# Qwiic_Multi_Port_Board.net
KiCad netlist of a schematic drawn in EAGLE
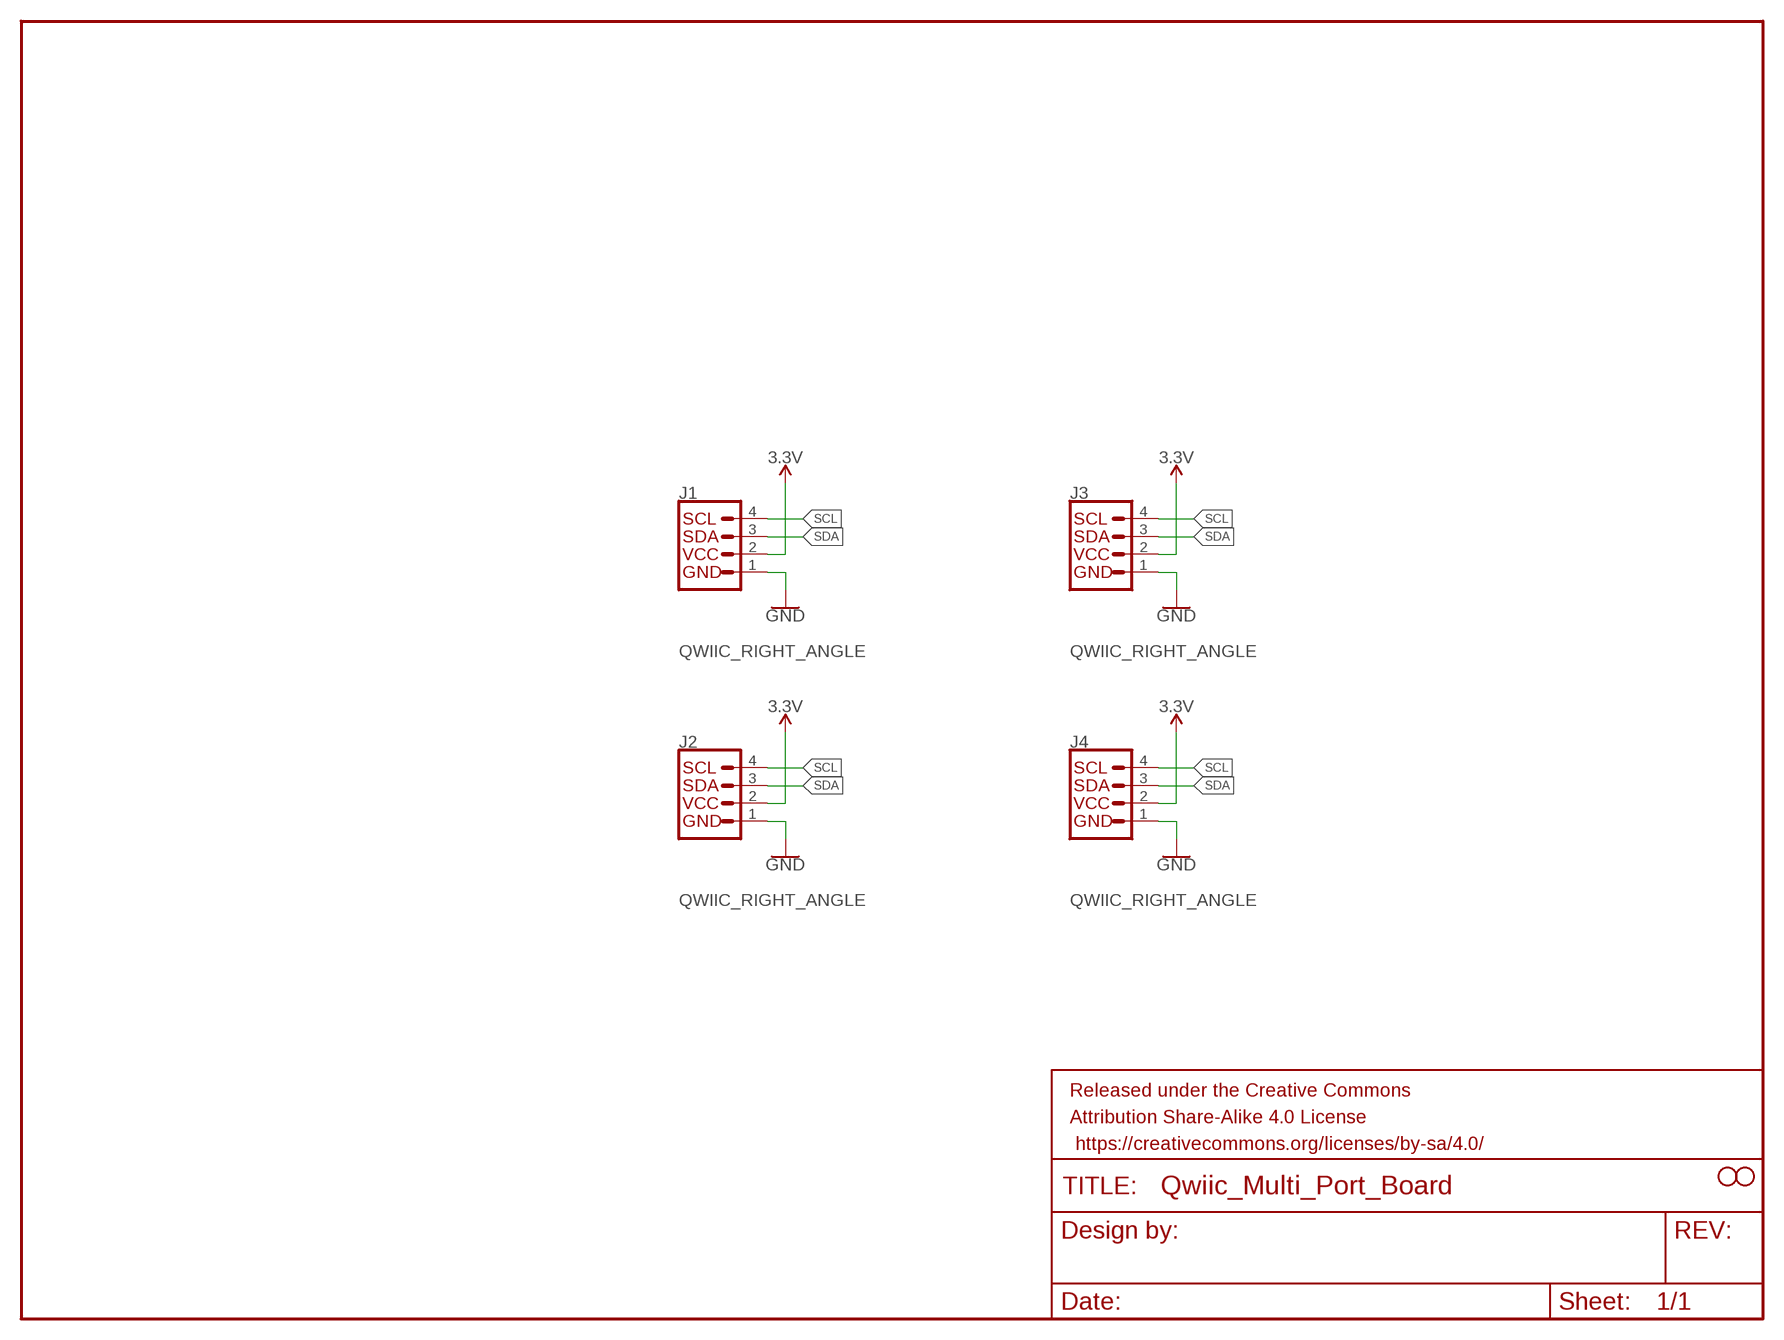
[diagram p0: schematic, sheet 1]

(export (version "E")
  (design (tool "Eeschema 10.0.6"))
  (components
    (comp (ref "FRAME1")
      (value "FRAME-LETTER")
      (footprint "eagle-import:CREATIVE_COMMONS")
      (libsource (lib "eagle-import") (part "FRAME-LETTER"))
    )
    (comp (ref "H1")
      (value "STAND-OFFTIGHT")
      (footprint "eagle-import:STAND-OFF-TIGHT")
      (libsource (lib "eagle-import") (part "STAND-OFFTIGHT"))
    )
    (comp (ref "H2")
      (value "STAND-OFFTIGHT")
      (footprint "eagle-import:STAND-OFF-TIGHT")
      (libsource (lib "eagle-import") (part "STAND-OFFTIGHT"))
    )
    (comp (ref "J1")
      (value "QWIIC_RIGHT_ANGLE")
      (footprint "eagle-import:JST04_1MM_RA")
      (libsource (lib "eagle-import") (part "QWIIC_CONNECTORJS-1MM"))
    )
    (comp (ref "J2")
      (value "QWIIC_RIGHT_ANGLE")
      (footprint "eagle-import:JST04_1MM_RA")
      (libsource (lib "eagle-import") (part "QWIIC_CONNECTORJS-1MM"))
    )
    (comp (ref "J3")
      (value "QWIIC_RIGHT_ANGLE")
      (footprint "eagle-import:JST04_1MM_RA")
      (libsource (lib "eagle-import") (part "QWIIC_CONNECTORJS-1MM"))
    )
    (comp (ref "J4")
      (value "QWIIC_RIGHT_ANGLE")
      (footprint "eagle-import:JST04_1MM_RA")
      (libsource (lib "eagle-import") (part "QWIIC_CONNECTORJS-1MM"))
    )
  )
  (nets
    (net (code "1") (name "3.3V") (class "Default")
      (node (ref "J1") (pin "2") (pinfunction "2_2") (pintype "power_in"))
      (node (ref "J2") (pin "2") (pinfunction "2_2") (pintype "power_in"))
      (node (ref "J3") (pin "2") (pinfunction "2_2") (pintype "power_in"))
      (node (ref "J4") (pin "2") (pinfunction "2_2") (pintype "power_in"))
    )
    (net (code "2") (name "GND") (class "Default")
      (node (ref "J1") (pin "1") (pinfunction "1_1") (pintype "power_in"))
      (node (ref "J2") (pin "1") (pinfunction "1_1") (pintype "power_in"))
      (node (ref "J3") (pin "1") (pinfunction "1_1") (pintype "power_in"))
      (node (ref "J4") (pin "1") (pinfunction "1_1") (pintype "power_in"))
    )
    (net (code "3") (name "SCL") (class "Default")
      (node (ref "J1") (pin "4") (pinfunction "4_4") (pintype "passive"))
      (node (ref "J2") (pin "4") (pinfunction "4_4") (pintype "passive"))
      (node (ref "J3") (pin "4") (pinfunction "4_4") (pintype "passive"))
      (node (ref "J4") (pin "4") (pinfunction "4_4") (pintype "passive"))
    )
    (net (code "4") (name "SDA") (class "Default")
      (node (ref "J1") (pin "3") (pinfunction "3_3") (pintype "passive"))
      (node (ref "J2") (pin "3") (pinfunction "3_3") (pintype "passive"))
      (node (ref "J3") (pin "3") (pinfunction "3_3") (pintype "passive"))
      (node (ref "J4") (pin "3") (pinfunction "3_3") (pintype "passive"))
    )
  )
)
